# ProPrj__Lab8__2025-11-21.net
KiCad netlist of a schematic drawn in EasyEDA Pro
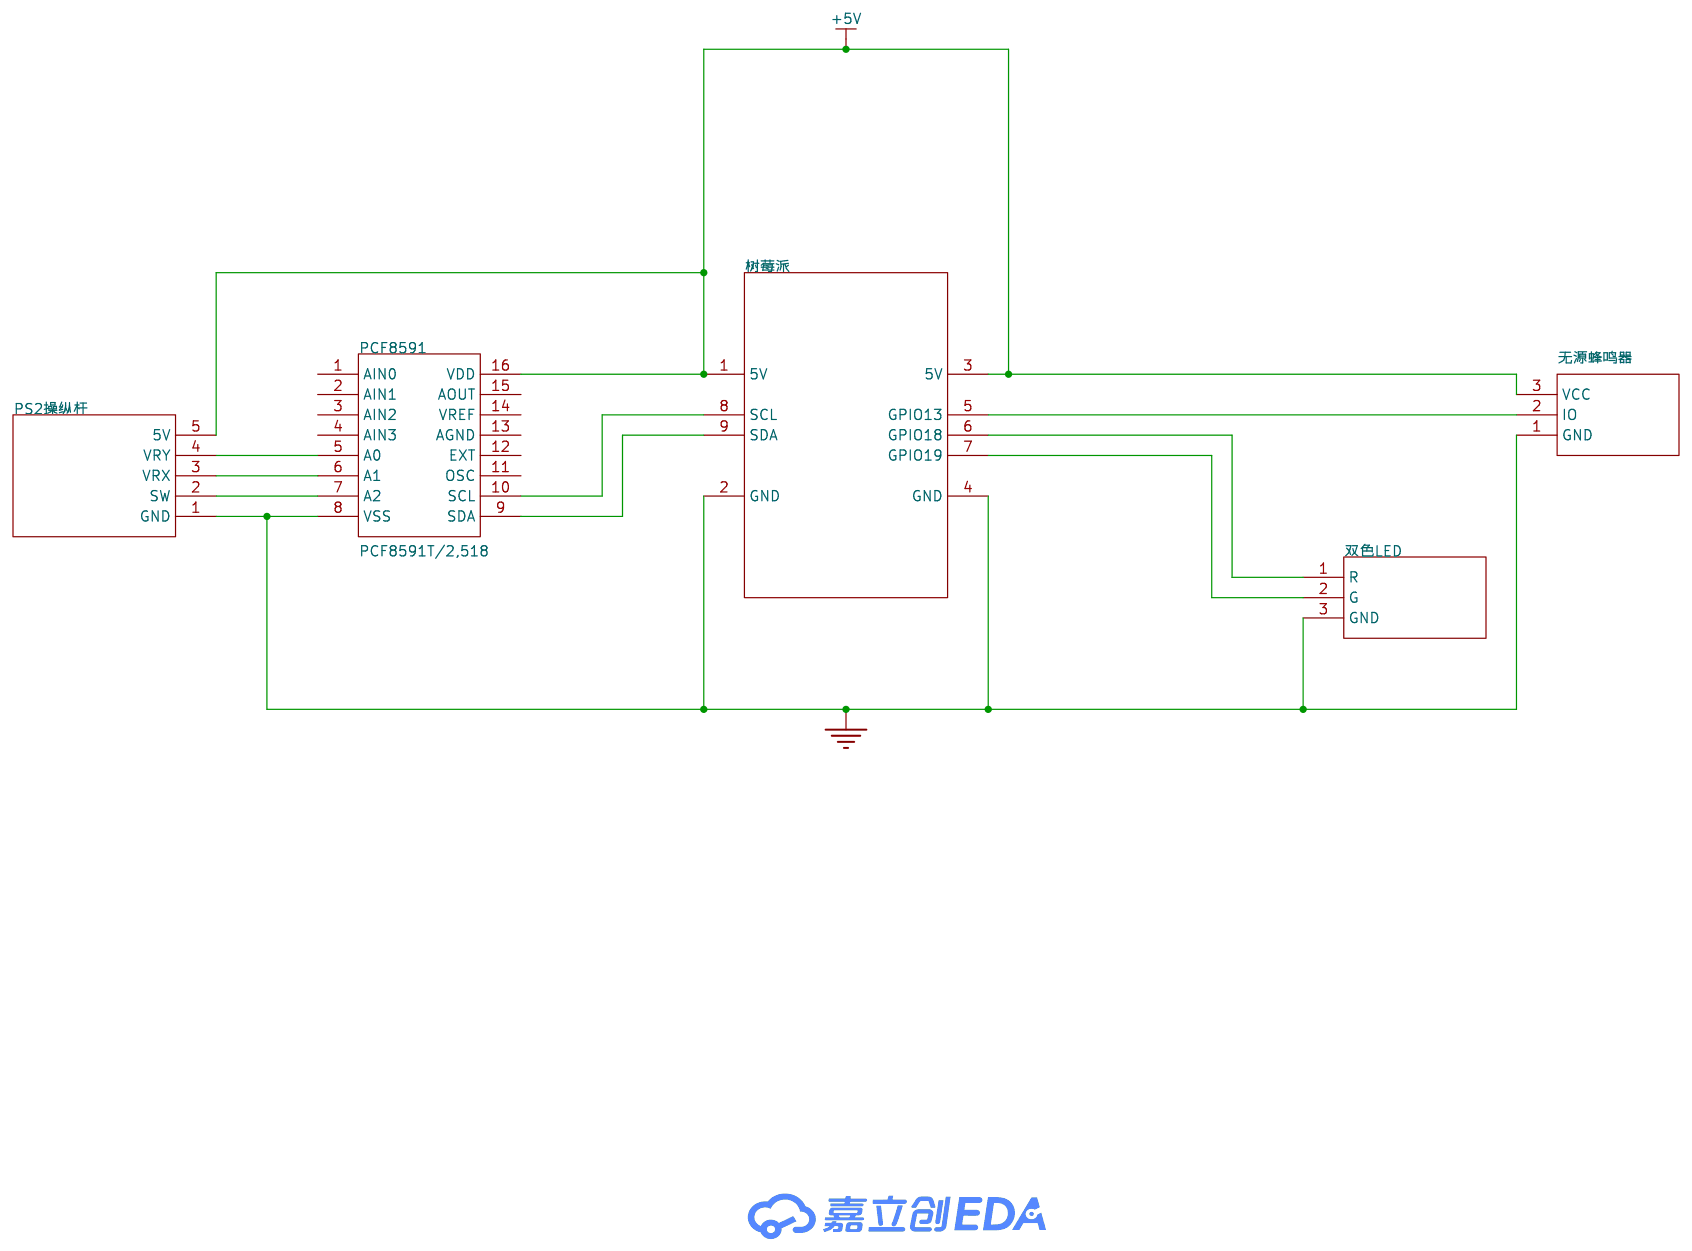
[diagram p0: schematic sheet]

(export (version "E")
  (design (tool "Eeschema 10.0.6"))
  (components
    (comp (ref "PCF8591")
      (value "PCF8591T/2,518")
      (footprint "easyedapro:SOIC-16_L10.3-W7.5-P1.27-LS10.3-BL")
      (fields (field (name "Manufacturer") "NXP(恩智浦)"))
      (libsource (lib "easyedapro") (part "PCF8591T"))
    )
    (comp (ref "PS2操纵杆") (value "~") (libsource (lib "easyedapro") (part "操纵杆示意图")))
    (comp (ref "双色LED") (value "~") (libsource (lib "easyedapro") (part "双色LED示意")))
    (comp (ref "无源蜂鸣器") (value "~") (libsource (lib "easyedapro") (part "无源蜂鸣器示意图")))
    (comp (ref "树莓派") (value "~") (libsource (lib "easyedapro") (part "树莓派示意图")))
  )
  (nets
    (net (code "1") (name "+5V") (class "Default")
      (node (ref "PCF8591") (pin "16") (pinfunction "VDD_16") (pintype "unspecified"))
      (node (ref "PS2操纵杆") (pin "5") (pinfunction "5V_5") (pintype "input"))
      (node (ref "无源蜂鸣器") (pin "3") (pinfunction "VCC_3") (pintype "input"))
      (node (ref "树莓派") (pin "1") (pinfunction "5V_1") (pintype "input"))
      (node (ref "树莓派") (pin "3") (pinfunction "5V_3") (pintype "input"))
    )
    (net (code "2") (name "GND") (class "Default")
      (node (ref "PCF8591") (pin "8") (pinfunction "VSS_8") (pintype "unspecified"))
      (node (ref "PS2操纵杆") (pin "1") (pinfunction "GND_1") (pintype "input"))
      (node (ref "双色LED") (pin "3") (pinfunction "GND_3") (pintype "input"))
      (node (ref "无源蜂鸣器") (pin "1") (pinfunction "GND_1") (pintype "input"))
      (node (ref "树莓派") (pin "2") (pinfunction "GND_2") (pintype "input"))
      (node (ref "树莓派") (pin "4") (pinfunction "GND_4") (pintype "input"))
    )
    (net (code "3") (name "Net-(PCF8591-A0)") (class "Default")
      (node (ref "PCF8591") (pin "5") (pinfunction "A0_5") (pintype "unspecified"))
      (node (ref "PS2操纵杆") (pin "4") (pinfunction "VRY_4") (pintype "input"))
    )
    (net (code "4") (name "Net-(PCF8591-A1)") (class "Default")
      (node (ref "PCF8591") (pin "6") (pinfunction "A1_6") (pintype "unspecified"))
      (node (ref "PS2操纵杆") (pin "3") (pinfunction "VRX_3") (pintype "input"))
    )
    (net (code "5") (name "Net-(PCF8591-A2)") (class "Default")
      (node (ref "PCF8591") (pin "7") (pinfunction "A2_7") (pintype "unspecified"))
      (node (ref "PS2操纵杆") (pin "2") (pinfunction "SW_2") (pintype "input"))
    )
    (net (code "6") (name "Net-(PCF8591-SCL)") (class "Default")
      (node (ref "PCF8591") (pin "10") (pinfunction "SCL_10") (pintype "unspecified"))
      (node (ref "树莓派") (pin "8") (pinfunction "SCL_8") (pintype "input"))
    )
    (net (code "7") (name "Net-(PCF8591-SDA)") (class "Default")
      (node (ref "PCF8591") (pin "9") (pinfunction "SDA_9") (pintype "unspecified"))
      (node (ref "树莓派") (pin "9") (pinfunction "SDA_9") (pintype "input"))
    )
    (net (code "8") (name "Net-(双色LED-G)") (class "Default")
      (node (ref "双色LED") (pin "2") (pinfunction "G_2") (pintype "input"))
      (node (ref "树莓派") (pin "7") (pinfunction "GPIO19_7") (pintype "input"))
    )
    (net (code "9") (name "Net-(双色LED-R)") (class "Default")
      (node (ref "双色LED") (pin "1") (pinfunction "R_1") (pintype "input"))
      (node (ref "树莓派") (pin "6") (pinfunction "GPIO18_6") (pintype "input"))
    )
    (net (code "10") (name "Net-(无源蜂鸣器-IO)") (class "Default")
      (node (ref "无源蜂鸣器") (pin "2") (pinfunction "IO_2") (pintype "input"))
      (node (ref "树莓派") (pin "5") (pinfunction "GPIO13_5") (pintype "input"))
    )
    (net (code "11") (name "unconnected-(PCF8591-AGND-Pad13)") (class "Default")
      (node (ref "PCF8591") (pin "13") (pinfunction "AGND_13") (pintype "unspecified"))
    )
    (net (code "12") (name "unconnected-(PCF8591-AIN0-Pad1)") (class "Default")
      (node (ref "PCF8591") (pin "1") (pinfunction "AIN0_1") (pintype "unspecified"))
    )
    (net (code "13") (name "unconnected-(PCF8591-AIN1-Pad2)") (class "Default")
      (node (ref "PCF8591") (pin "2") (pinfunction "AIN1_2") (pintype "unspecified"))
    )
    (net (code "14") (name "unconnected-(PCF8591-AIN2-Pad3)") (class "Default")
      (node (ref "PCF8591") (pin "3") (pinfunction "AIN2_3") (pintype "unspecified"))
    )
    (net (code "15") (name "unconnected-(PCF8591-AIN3-Pad4)") (class "Default")
      (node (ref "PCF8591") (pin "4") (pinfunction "AIN3_4") (pintype "unspecified"))
    )
    (net (code "16") (name "unconnected-(PCF8591-AOUT-Pad15)") (class "Default")
      (node (ref "PCF8591") (pin "15") (pinfunction "AOUT_15") (pintype "unspecified"))
    )
    (net (code "17") (name "unconnected-(PCF8591-EXT-Pad12)") (class "Default")
      (node (ref "PCF8591") (pin "12") (pinfunction "EXT_12") (pintype "unspecified"))
    )
    (net (code "18") (name "unconnected-(PCF8591-OSC-Pad11)") (class "Default")
      (node (ref "PCF8591") (pin "11") (pinfunction "OSC_11") (pintype "unspecified"))
    )
    (net (code "19") (name "unconnected-(PCF8591-VREF-Pad14)") (class "Default")
      (node (ref "PCF8591") (pin "14") (pinfunction "VREF_14") (pintype "unspecified"))
    )
  )
)
